# Adafruit_High_Voltage_UPDI_Friend.net
KiCad netlist of a schematic drawn in EAGLE
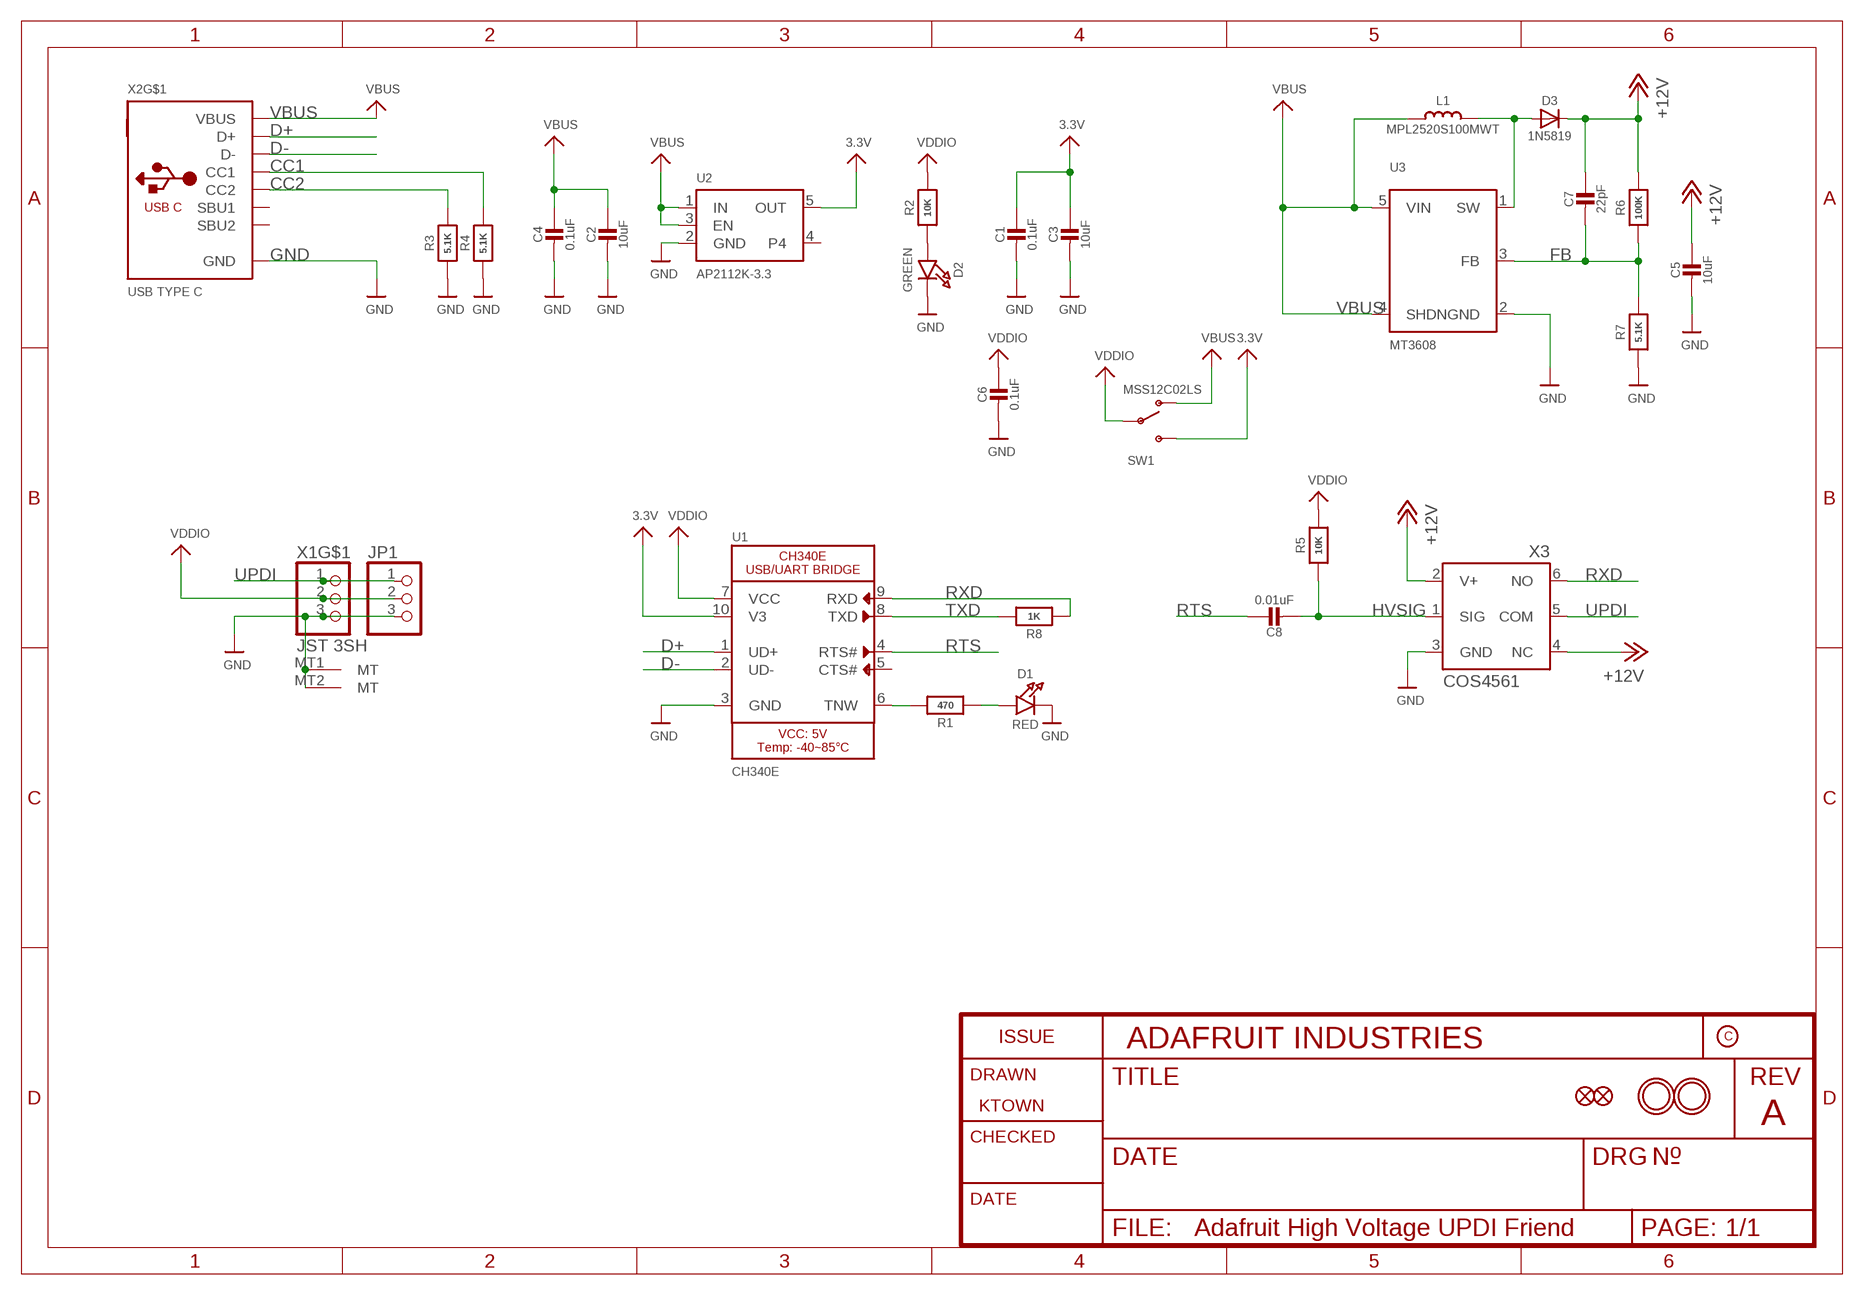
[diagram p0: schematic, sheet 1]

(export (version "E")
  (design (tool "Eeschema 10.0.6"))
  (components
    (comp (ref "C1")
      (value "0.1uF")
      (footprint "eagle-import:0603-NO")
      (libsource (lib "eagle-import") (part "CAP_CERAMIC0603_NO"))
    )
    (comp (ref "C2")
      (value "10uF")
      (footprint "eagle-import:0805-NO")
      (libsource (lib "eagle-import") (part "CAP_CERAMIC0805-NOOUTLINE"))
    )
    (comp (ref "C3")
      (value "10uF")
      (footprint "eagle-import:0805-NO")
      (libsource (lib "eagle-import") (part "CAP_CERAMIC0805-NOOUTLINE"))
    )
    (comp (ref "C4")
      (value "0.1uF")
      (footprint "eagle-import:0603-NO")
      (libsource (lib "eagle-import") (part "CAP_CERAMIC0603_NO"))
    )
    (comp (ref "C5")
      (value "10uF")
      (footprint "eagle-import:0805-NO")
      (libsource (lib "eagle-import") (part "CAP_CERAMIC0805-NOOUTLINE"))
    )
    (comp (ref "C6")
      (value "0.1uF")
      (footprint "eagle-import:0603-NO")
      (libsource (lib "eagle-import") (part "CAP_CERAMIC0603_NO"))
    )
    (comp (ref "C7")
      (value "22pF")
      (footprint "eagle-import:0603-NO")
      (libsource (lib "eagle-import") (part "CAP_CERAMIC0603_NO"))
    )
    (comp (ref "C8")
      (value "0.01uF")
      (footprint "eagle-import:0603-NO")
      (libsource (lib "eagle-import") (part "CAP_CERAMIC0603_NO"))
    )
    (comp (ref "D1")
      (value "RED")
      (footprint "eagle-import:CHIPLED_0603_NOOUTLINE")
      (libsource (lib "eagle-import") (part "LED0603_NOOUTLINE"))
    )
    (comp (ref "D2")
      (value "GREEN")
      (footprint "eagle-import:CHIPLED_0603_NOOUTLINE")
      (libsource (lib "eagle-import") (part "LED0603_NOOUTLINE"))
    )
    (comp (ref "D3")
      (value "1N5819")
      (footprint "eagle-import:SOD-323")
      (libsource (lib "eagle-import") (part "DIODESOD-323"))
    )
    (comp (ref "FID1")
      (value "FIDUCIAL_1MM")
      (footprint "eagle-import:FIDUCIAL_1MM")
      (libsource (lib "eagle-import") (part "FIDUCIAL_1MM"))
    )
    (comp (ref "FID2")
      (value "FIDUCIAL_1MM")
      (footprint "eagle-import:FIDUCIAL_1MM")
      (libsource (lib "eagle-import") (part "FIDUCIAL_1MM"))
    )
    (comp (ref "JP1")
      (value "HEADER-1X376MIL")
      (footprint "eagle-import:1X03_ROUND_76")
      (libsource (lib "eagle-import") (part "HEADER-1X376MIL"))
    )
    (comp (ref "L1")
      (value "MPL2520S100MWT")
      (footprint "eagle-import:INDUCTOR_1007")
      (libsource (lib "eagle-import") (part "INDUCTOR"))
    )
    (comp (ref "R1")
      (value "470")
      (footprint "eagle-import:0603-NO")
      (libsource (lib "eagle-import") (part "RESISTOR_0603_NOOUT"))
    )
    (comp (ref "R2")
      (value "10K")
      (footprint "eagle-import:0603-NO")
      (libsource (lib "eagle-import") (part "RESISTOR_0603_NOOUT"))
    )
    (comp (ref "R3")
      (value "5.1K")
      (footprint "eagle-import:0603-NO")
      (libsource (lib "eagle-import") (part "RESISTOR_0603_NOOUT"))
    )
    (comp (ref "R4")
      (value "5.1K")
      (footprint "eagle-import:0603-NO")
      (libsource (lib "eagle-import") (part "RESISTOR_0603_NOOUT"))
    )
    (comp (ref "R5")
      (value "10K")
      (footprint "eagle-import:0603-NO")
      (libsource (lib "eagle-import") (part "RESISTOR_0603_NOOUT"))
    )
    (comp (ref "R6")
      (value "100K")
      (footprint "eagle-import:0603-NO")
      (libsource (lib "eagle-import") (part "RESISTOR_0603_NOOUT"))
    )
    (comp (ref "R7")
      (value "5.1K")
      (footprint "eagle-import:0603-NO")
      (libsource (lib "eagle-import") (part "RESISTOR_0603_NOOUT"))
    )
    (comp (ref "R8")
      (value "1K")
      (footprint "eagle-import:0603-NO")
      (libsource (lib "eagle-import") (part "RESISTOR_0603_NOOUT"))
    )
    (comp (ref "SW1")
      (value "MSS12C02LS")
      (footprint "eagle-import:SPDT_SMT_SSSS811101")
      (libsource (lib "eagle-import") (part "SWITCH_SPDT"))
    )
    (comp (ref "U$18")
      (value "MOUNTINGHOLE2.0")
      (footprint "eagle-import:MOUNTINGHOLE_2.0_PLATED")
      (libsource (lib "eagle-import") (part "MOUNTINGHOLE2.0"))
    )
    (comp (ref "U$19")
      (value "MOUNTINGHOLE2.0")
      (footprint "eagle-import:MOUNTINGHOLE_2.0_PLATED")
      (libsource (lib "eagle-import") (part "MOUNTINGHOLE2.0"))
    )
    (comp (ref "U1")
      (value "CH340E")
      (footprint "eagle-import:MSOP10")
      (libsource (lib "eagle-import") (part "CH340E_MSOP10"))
    )
    (comp (ref "U2")
      (value "AP2112K-3.3")
      (footprint "eagle-import:SOT23-5")
      (fields (field (name "JLC_ROTATION") "0"))
      (libsource (lib "eagle-import") (part "VREG_SOT23-5"))
    )
    (comp (ref "U3")
      (value "MT3608")
      (footprint "eagle-import:SOT23-6")
      (libsource (lib "eagle-import") (part "VREG_BOOST_5PIN_SOT236"))
    )
    (comp (ref "X1")
      (value "JST 3SH")
      (footprint "eagle-import:JST_SH3")
      (libsource (lib "eagle-import") (part "CON_JST_SH_3PINHORZ"))
    )
    (comp (ref "X2")
      (value "USB TYPE C")
      (footprint "eagle-import:USB_C_CUSB31-CFM2AX-01-X")
      (libsource (lib "eagle-import") (part "USB_C"))
    )
    (comp (ref "X3")
      (value "COS4561")
      (footprint "eagle-import:SOT23-6")
      (libsource (lib "eagle-import") (part "COS4561"))
    )
  )
  (nets
    (net (code "1") (name "+12V") (class "Default")
      (node (ref "C5") (pin "1") (pinfunction "1_1") (pintype "passive"))
      (node (ref "C7") (pin "1") (pinfunction "1_1") (pintype "passive"))
      (node (ref "D3") (pin "C") (pinfunction "C_C") (pintype "passive"))
      (node (ref "R6") (pin "2") (pinfunction "2_2") (pintype "passive"))
      (node (ref "X3") (pin "2") (pinfunction "V+_2") (pintype "power_in"))
      (node (ref "X3") (pin "4") (pinfunction "NC_4") (pintype "bidirectional"))
    )
    (net (code "2") (name "/CC1") (class "Default")
      (node (ref "R4") (pin "2") (pinfunction "2_2") (pintype "passive"))
      (node (ref "X2") (pin "A5") (pinfunction "CC1_A5") (pintype "bidirectional"))
    )
    (net (code "3") (name "/CC2") (class "Default")
      (node (ref "R3") (pin "2") (pinfunction "2_2") (pintype "passive"))
      (node (ref "X2") (pin "B5") (pinfunction "CC2_B5") (pintype "bidirectional"))
    )
    (net (code "4") (name "/D+") (class "Default")
      (node (ref "U1") (pin "1") (pinfunction "UD+_1") (pintype "bidirectional"))
      (node (ref "X2") (pin "A6") (pinfunction "D+_A6") (pintype "bidirectional"))
      (node (ref "X2") (pin "B6") (pinfunction "D+_B6") (pintype "bidirectional"))
    )
    (net (code "5") (name "/D-") (class "Default")
      (node (ref "U1") (pin "2") (pinfunction "UD-_2") (pintype "bidirectional"))
      (node (ref "X2") (pin "A7") (pinfunction "D-_A7") (pintype "bidirectional"))
      (node (ref "X2") (pin "B7") (pinfunction "D-_B7") (pintype "bidirectional"))
    )
    (net (code "6") (name "/FB") (class "Default")
      (node (ref "C7") (pin "2") (pinfunction "2_2") (pintype "passive"))
      (node (ref "R6") (pin "1") (pinfunction "1_1") (pintype "passive"))
      (node (ref "R7") (pin "2") (pinfunction "2_2") (pintype "passive"))
      (node (ref "U3") (pin "3") (pinfunction "FB_3") (pintype "bidirectional"))
    )
    (net (code "7") (name "/HVSIG") (class "Default")
      (node (ref "C8") (pin "2") (pinfunction "2_2") (pintype "passive"))
      (node (ref "R5") (pin "1") (pinfunction "1_1") (pintype "passive"))
      (node (ref "X3") (pin "1") (pinfunction "SIG_1") (pintype "input"))
    )
    (net (code "8") (name "/RTS") (class "Default")
      (node (ref "C8") (pin "1") (pinfunction "1_1") (pintype "passive"))
      (node (ref "U1") (pin "4") (pinfunction "RTS#_4") (pintype "output"))
    )
    (net (code "9") (name "/RXD") (class "Default")
      (node (ref "R8") (pin "2") (pinfunction "2_2") (pintype "passive"))
      (node (ref "U1") (pin "9") (pinfunction "RXD_9") (pintype "input"))
      (node (ref "X3") (pin "6") (pinfunction "NO_6") (pintype "bidirectional"))
    )
    (net (code "10") (name "/TXD") (class "Default")
      (node (ref "R8") (pin "1") (pinfunction "1_1") (pintype "passive"))
      (node (ref "U1") (pin "8") (pinfunction "TXD_8") (pintype "output"))
    )
    (net (code "11") (name "/UPDI") (class "Default")
      (node (ref "JP1") (pin "1") (pinfunction "1_1") (pintype "passive"))
      (node (ref "X1") (pin "1") (pinfunction "1_1") (pintype "passive"))
      (node (ref "X3") (pin "5") (pinfunction "COM_5") (pintype "bidirectional"))
    )
    (net (code "12") (name "3.3V") (class "Default")
      (node (ref "C1") (pin "1") (pinfunction "1_1") (pintype "passive"))
      (node (ref "C3") (pin "1") (pinfunction "1_1") (pintype "passive"))
      (node (ref "SW1") (pin "C") (pinfunction "S_C") (pintype "passive"))
      (node (ref "U1") (pin "10") (pinfunction "V3_10") (pintype "bidirectional"))
      (node (ref "U2") (pin "5") (pinfunction "OUT_5") (pintype "power_in"))
    )
    (net (code "13") (name "GND") (class "Default")
      (node (ref "C1") (pin "2") (pinfunction "2_2") (pintype "passive"))
      (node (ref "C2") (pin "2") (pinfunction "2_2") (pintype "passive"))
      (node (ref "C3") (pin "2") (pinfunction "2_2") (pintype "passive"))
      (node (ref "C4") (pin "2") (pinfunction "2_2") (pintype "passive"))
      (node (ref "C5") (pin "2") (pinfunction "2_2") (pintype "passive"))
      (node (ref "C6") (pin "2") (pinfunction "2_2") (pintype "passive"))
      (node (ref "D1") (pin "C") (pinfunction "C_C") (pintype "passive"))
      (node (ref "D2") (pin "C") (pinfunction "C_C") (pintype "passive"))
      (node (ref "JP1") (pin "3") (pinfunction "3_3") (pintype "passive"))
      (node (ref "R3") (pin "1") (pinfunction "1_1") (pintype "passive"))
      (node (ref "R4") (pin "1") (pinfunction "1_1") (pintype "passive"))
      (node (ref "R7") (pin "1") (pinfunction "1_1") (pintype "passive"))
      (node (ref "U1") (pin "3") (pinfunction "GND_3") (pintype "power_in"))
      (node (ref "U2") (pin "2") (pinfunction "GND_2") (pintype "power_in"))
      (node (ref "U3") (pin "2") (pinfunction "GND_2") (pintype "bidirectional"))
      (node (ref "X1") (pin "3") (pinfunction "3_3") (pintype "passive"))
      (node (ref "X1") (pin "MT1") (pinfunction "MT_MT1") (pintype "bidirectional"))
      (node (ref "X1") (pin "MT2") (pinfunction "MT_MT2") (pintype "bidirectional"))
      (node (ref "X2") (pin "A1B12") (pinfunction "GND_A1B12") (pintype "power_in"))
      (node (ref "X2") (pin "B1A12") (pinfunction "GND_B1A12") (pintype "power_in"))
      (node (ref "X3") (pin "3") (pinfunction "GND_3") (pintype "power_in"))
    )
    (net (code "14") (name "Net-(D1-PadA)") (class "Default")
      (node (ref "D1") (pin "A") (pinfunction "A_A") (pintype "passive"))
      (node (ref "R1") (pin "1") (pinfunction "1_1") (pintype "passive"))
    )
    (net (code "15") (name "Net-(D2-PadA)") (class "Default")
      (node (ref "D2") (pin "A") (pinfunction "A_A") (pintype "passive"))
      (node (ref "R2") (pin "1") (pinfunction "1_1") (pintype "passive"))
    )
    (net (code "16") (name "Net-(L1-2)") (class "Default")
      (node (ref "D3") (pin "A") (pinfunction "A_A") (pintype "passive"))
      (node (ref "L1") (pin "P$2") (pinfunction "2_P$2") (pintype "passive"))
      (node (ref "U3") (pin "1") (pinfunction "SW_1") (pintype "bidirectional"))
    )
    (net (code "17") (name "Net-(U1-TNW)") (class "Default")
      (node (ref "R1") (pin "2") (pinfunction "2_2") (pintype "passive"))
      (node (ref "U1") (pin "6") (pinfunction "TNW_6") (pintype "output"))
    )
    (net (code "18") (name "VBUS") (class "Default")
      (node (ref "C2") (pin "1") (pinfunction "1_1") (pintype "passive"))
      (node (ref "C4") (pin "1") (pinfunction "1_1") (pintype "passive"))
      (node (ref "L1") (pin "P$1") (pinfunction "1_P$1") (pintype "passive"))
      (node (ref "SW1") (pin "A") (pinfunction "O_A") (pintype "passive"))
      (node (ref "U2") (pin "1") (pinfunction "IN_1") (pintype "power_in"))
      (node (ref "U2") (pin "3") (pinfunction "EN_3") (pintype "input"))
      (node (ref "U3") (pin "4") (pinfunction "SHDN_4") (pintype "bidirectional"))
      (node (ref "U3") (pin "5") (pinfunction "VIN_5") (pintype "bidirectional"))
      (node (ref "X2") (pin "A4B9") (pinfunction "VBUS_A4B9") (pintype "power_in"))
      (node (ref "X2") (pin "B4A9") (pinfunction "VBUS_B4A9") (pintype "power_in"))
    )
    (net (code "19") (name "VDDIO") (class "Default")
      (node (ref "C6") (pin "1") (pinfunction "1_1") (pintype "passive"))
      (node (ref "JP1") (pin "2") (pinfunction "2_2") (pintype "passive"))
      (node (ref "R2") (pin "2") (pinfunction "2_2") (pintype "passive"))
      (node (ref "R5") (pin "2") (pinfunction "2_2") (pintype "passive"))
      (node (ref "SW1") (pin "B") (pinfunction "P_B") (pintype "passive"))
      (node (ref "U1") (pin "7") (pinfunction "VCC_7") (pintype "power_in"))
      (node (ref "X1") (pin "2") (pinfunction "2_2") (pintype "passive"))
    )
    (net (code "20") (name "unconnected-(U1-CTS#-Pad5)") (class "Default")
      (node (ref "U1") (pin "5") (pinfunction "CTS#_5") (pintype "input"))
    )
    (net (code "21") (name "unconnected-(U2-P4-Pad4)") (class "Default")
      (node (ref "U2") (pin "4") (pinfunction "P4_4") (pintype "bidirectional"))
    )
    (net (code "22") (name "unconnected-(X2A-SBU1-PadA8)") (class "Default")
      (node (ref "X2") (pin "A8") (pinfunction "SBU1_A8") (pintype "bidirectional"))
    )
    (net (code "23") (name "unconnected-(X2A-SBU2-PadB8)") (class "Default")
      (node (ref "X2") (pin "B8") (pinfunction "SBU2_B8") (pintype "bidirectional"))
    )
  )
)
